# SOC_COMPHY_USB.net
KiCad netlist of a schematic drawn in Altium Designer
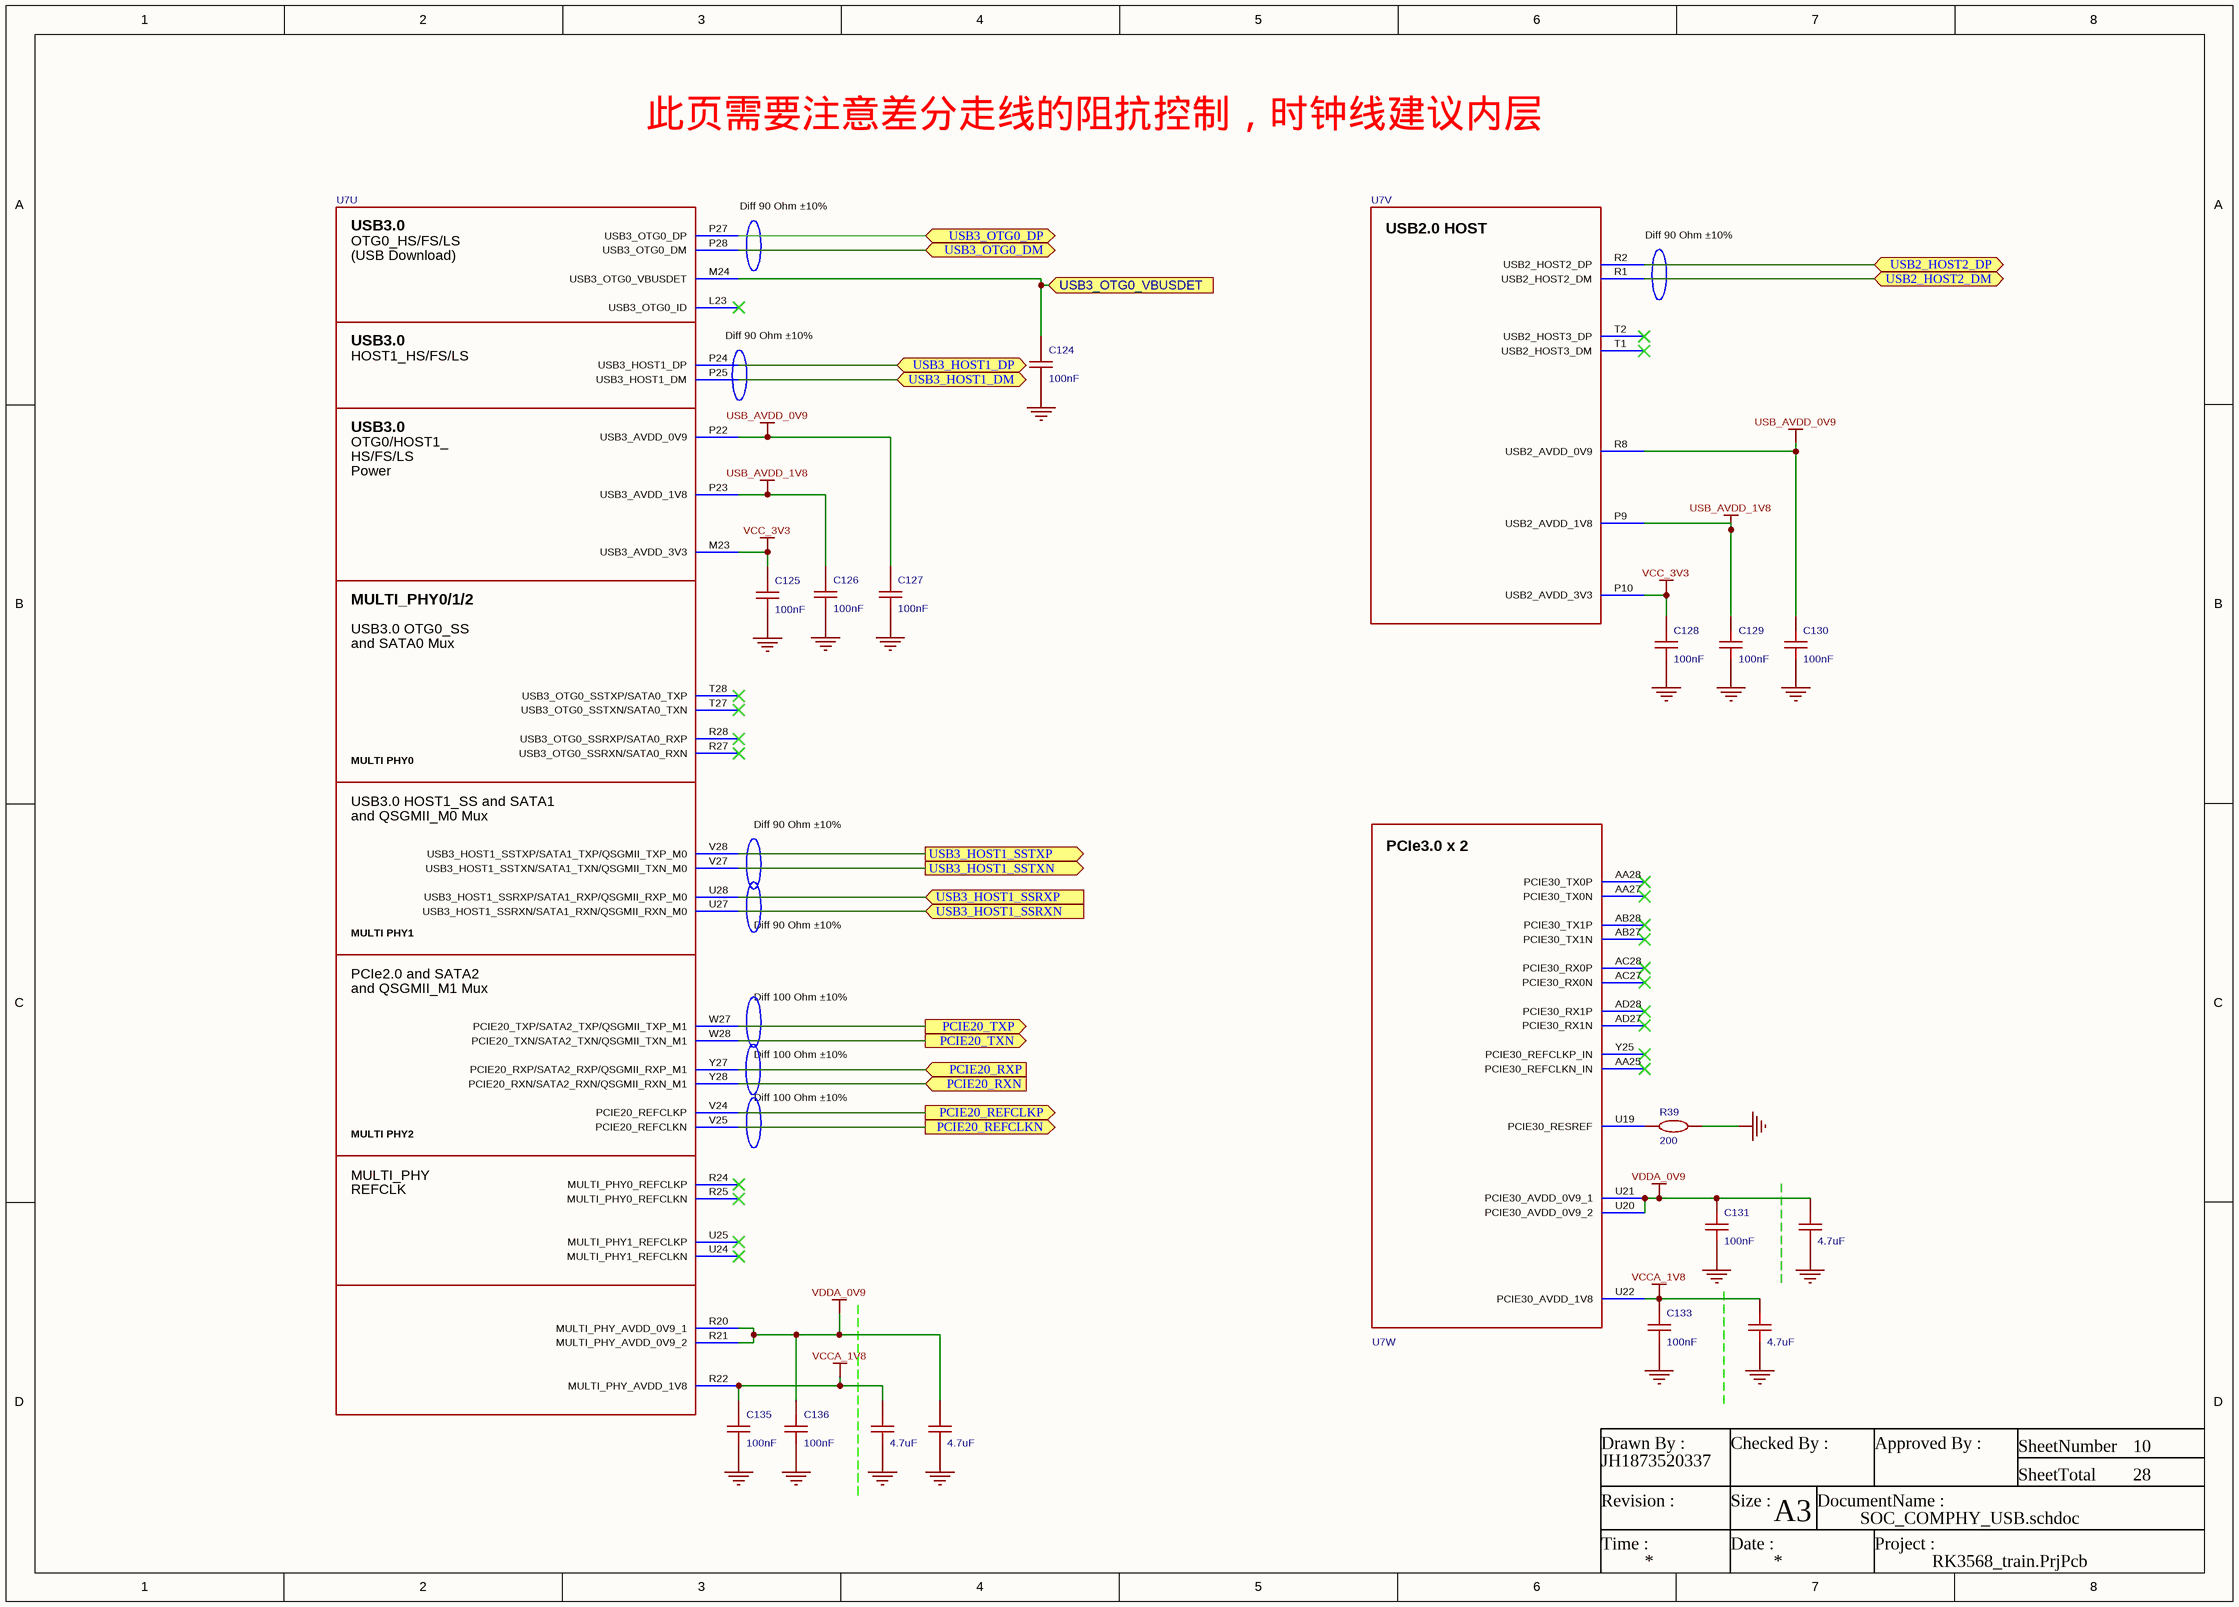
[diagram p0: SOC_COMPHY_USB.schdoc]

(export (version "E")
  (design (tool "Eeschema 10.0.6"))
  (components
    (comp (ref "C124")
      (value "100nF")
      (footprint "C0201")
      (description "容值:4.7uF;精度:±20%;额定电压:6.3V;温度系数:X5R;")
      (fields
        (field (name "MANUFACTURER") "muRata(村田)")
        (field (name "MANUFACTURERPART") "GRM035R60J475ME15D")
      )
      (libsource (lib "altium-import") (part "root_0_GRM035R60J475ME15D_"))
    )
    (comp (ref "C125")
      (value "100nF")
      (footprint "C0201")
      (description "容值:4.7uF;精度:±20%;额定电压:6.3V;温度系数:X5R;")
      (fields
        (field (name "MANUFACTURER") "muRata(村田)")
        (field (name "MANUFACTURERPART") "GRM035R60J475ME15D")
      )
      (libsource (lib "altium-import") (part "root_0_GRM035R60J475ME15D_"))
    )
    (comp (ref "C126")
      (value "100nF")
      (footprint "C0201")
      (description "容值:4.7uF;精度:±20%;额定电压:6.3V;温度系数:X5R;")
      (fields
        (field (name "MANUFACTURER") "muRata(村田)")
        (field (name "MANUFACTURERPART") "GRM035R60J475ME15D")
      )
      (libsource (lib "altium-import") (part "root_0_GRM035R60J475ME15D_"))
    )
    (comp (ref "C127")
      (value "100nF")
      (footprint "C0201")
      (description "容值:4.7uF;精度:±20%;额定电压:6.3V;温度系数:X5R;")
      (fields
        (field (name "MANUFACTURER") "muRata(村田)")
        (field (name "MANUFACTURERPART") "GRM035R60J475ME15D")
      )
      (libsource (lib "altium-import") (part "root_0_GRM035R60J475ME15D_"))
    )
    (comp (ref "C128")
      (value "100nF")
      (footprint "C0201")
      (description "容值:4.7uF;精度:±20%;额定电压:6.3V;温度系数:X5R;")
      (fields
        (field (name "MANUFACTURER") "muRata(村田)")
        (field (name "MANUFACTURERPART") "GRM035R60J475ME15D")
      )
      (libsource (lib "altium-import") (part "root_0_GRM035R60J475ME15D_"))
    )
    (comp (ref "C129")
      (value "100nF")
      (footprint "C0201")
      (description "容值:4.7uF;精度:±20%;额定电压:6.3V;温度系数:X5R;")
      (fields
        (field (name "MANUFACTURER") "muRata(村田)")
        (field (name "MANUFACTURERPART") "GRM035R60J475ME15D")
      )
      (libsource (lib "altium-import") (part "root_0_GRM035R60J475ME15D_"))
    )
    (comp (ref "C130")
      (value "100nF")
      (footprint "C0201")
      (description "容值:4.7uF;精度:±20%;额定电压:6.3V;温度系数:X5R;")
      (fields
        (field (name "MANUFACTURER") "muRata(村田)")
        (field (name "MANUFACTURERPART") "GRM035R60J475ME15D")
      )
      (libsource (lib "altium-import") (part "root_0_GRM035R60J475ME15D_"))
    )
    (comp (ref "C131")
      (value "100nF")
      (footprint "C0201")
      (description "容值:4.7uF;精度:±20%;额定电压:6.3V;温度系数:X5R;")
      (fields
        (field (name "MANUFACTURER") "muRata(村田)")
        (field (name "MANUFACTURERPART") "GRM035R60J475ME15D")
      )
      (libsource (lib "altium-import") (part "root_0_GRM035R60J475ME15D_"))
    )
    (comp (ref "C132")
      (value "4.7uF")
      (footprint "MYC0402")
      (description "容值:1uF;精度:±10%;额定电压:50V;材质(温度系数):X5R;")
      (fields (field (name "MANUFACTURER") "SAMSUNG(三星)") (field (name "MANUFACTURERPART") "CL10A105KB8NNNC"))
      (libsource (lib "altium-import") (part "root_1_CL10A105KB8NNNC_"))
    )
    (comp (ref "C133")
      (value "100nF")
      (footprint "C0201")
      (description "容值:4.7uF;精度:±20%;额定电压:6.3V;温度系数:X5R;")
      (fields
        (field (name "MANUFACTURER") "muRata(村田)")
        (field (name "MANUFACTURERPART") "GRM035R60J475ME15D")
      )
      (libsource (lib "altium-import") (part "root_0_GRM035R60J475ME15D_"))
    )
    (comp (ref "C134")
      (value "4.7uF")
      (footprint "MYC0402")
      (description "容值:1uF;精度:±10%;额定电压:50V;材质(温度系数):X5R;")
      (fields (field (name "MANUFACTURER") "SAMSUNG(三星)") (field (name "MANUFACTURERPART") "CL10A105KB8NNNC"))
      (libsource (lib "altium-import") (part "root_1_CL10A105KB8NNNC_"))
    )
    (comp (ref "C135")
      (value "100nF")
      (footprint "C0201")
      (description "容值:4.7uF;精度:±20%;额定电压:6.3V;温度系数:X5R;")
      (fields
        (field (name "MANUFACTURER") "muRata(村田)")
        (field (name "MANUFACTURERPART") "GRM035R60J475ME15D")
      )
      (libsource (lib "altium-import") (part "root_0_GRM035R60J475ME15D_"))
    )
    (comp (ref "C136")
      (value "100nF")
      (footprint "C0201")
      (description "容值:4.7uF;精度:±20%;额定电压:6.3V;温度系数:X5R;")
      (fields
        (field (name "MANUFACTURER") "muRata(村田)")
        (field (name "MANUFACTURERPART") "GRM035R60J475ME15D")
      )
      (libsource (lib "altium-import") (part "root_0_GRM035R60J475ME15D_"))
    )
    (comp (ref "C137")
      (value "4.7uF")
      (footprint "MYC0402")
      (description "容值:1uF;精度:±10%;额定电压:50V;材质(温度系数):X5R;")
      (fields (field (name "MANUFACTURER") "SAMSUNG(三星)") (field (name "MANUFACTURERPART") "CL10A105KB8NNNC"))
      (libsource (lib "altium-import") (part "root_1_CL10A105KB8NNNC_"))
    )
    (comp (ref "C138")
      (value "4.7uF")
      (footprint "MYC0402")
      (description "容值:1uF;精度:±10%;额定电压:50V;材质(温度系数):X5R;")
      (fields (field (name "MANUFACTURER") "SAMSUNG(三星)") (field (name "MANUFACTURERPART") "CL10A105KB8NNNC"))
      (libsource (lib "altium-import") (part "root_1_CL10A105KB8NNNC_"))
    )
    (comp (ref "R39")
      (value "200")
      (footprint "R0201")
      (libsource (lib "altium-import") (part "root_0_Res_0201_"))
    )
    (comp (ref "U7")
      (value "RK3568")
      (footprint "BGA-636_L19.0-W19.0-P0.65-BL")
      (libsource (lib "altium-import") (part "root_0_RK3568_"))
    )
  )
  (nets
    (net (code "1") (name "/PCIE20_REFCLKN") (class "Default")
      (node (ref "U7") (pin "V25") (pinfunction "PCIE20_REFCLKN_V25") (pintype "passive"))
    )
    (net (code "2") (name "/PCIE20_REFCLKP") (class "Default")
      (node (ref "U7") (pin "V24") (pinfunction "PCIE20_REFCLKP_V24") (pintype "passive"))
    )
    (net (code "3") (name "/PCIE20_RXN") (class "Default")
      (node (ref "U7") (pin "Y28") (pinfunction "PCIE20_RXN/SATA2_RXN/QSGMII_RXN_M1_Y28") (pintype "passive"))
    )
    (net (code "4") (name "/PCIE20_RXP") (class "Default")
      (node (ref "U7") (pin "Y27") (pinfunction "PCIE20_RXP/SATA2_RXP/QSGMII_RXP_M1_Y27") (pintype "passive"))
    )
    (net (code "5") (name "/PCIE20_TXN") (class "Default")
      (node (ref "U7") (pin "W28") (pinfunction "PCIE20_TXN/SATA2_TXN/QSGMII_TXN_M1_W28") (pintype "passive"))
    )
    (net (code "6") (name "/PCIE20_TXP") (class "Default")
      (node (ref "U7") (pin "W27") (pinfunction "PCIE20_TXP/SATA2_TXP/QSGMII_TXP_M1_W27") (pintype "passive"))
    )
    (net (code "7") (name "/USB2_HOST2_DM") (class "Default")
      (node (ref "U7") (pin "R1") (pinfunction "USB2_HOST2_DM_R1") (pintype "passive"))
    )
    (net (code "8") (name "/USB2_HOST2_DP") (class "Default")
      (node (ref "U7") (pin "R2") (pinfunction "USB2_HOST2_DP_R2") (pintype "passive"))
    )
    (net (code "9") (name "/USB3_HOST1_DM") (class "Default")
      (node (ref "U7") (pin "P25") (pinfunction "USB3_HOST1_DM_P25") (pintype "passive"))
    )
    (net (code "10") (name "/USB3_HOST1_DP") (class "Default")
      (node (ref "U7") (pin "P24") (pinfunction "USB3_HOST1_DP_P24") (pintype "passive"))
    )
    (net (code "11") (name "/USB3_HOST1_SSRXN") (class "Default")
      (node (ref "U7") (pin "U27") (pinfunction "USB3_HOST1_SSRXN/SATA1_RXN/QSGMII_RXN_M0_U27") (pintype "passive"))
    )
    (net (code "12") (name "/USB3_HOST1_SSRXP") (class "Default")
      (node (ref "U7") (pin "U28") (pinfunction "USB3_HOST1_SSRXP/SATA1_RXP/QSGMII_RXP_M0_U28") (pintype "passive"))
    )
    (net (code "13") (name "/USB3_HOST1_SSTXN") (class "Default")
      (node (ref "U7") (pin "V27") (pinfunction "USB3_HOST1_SSTXN/SATA1_TXN/QSGMII_TXN_M0_V27") (pintype "passive"))
    )
    (net (code "14") (name "/USB3_HOST1_SSTXP") (class "Default")
      (node (ref "U7") (pin "V28") (pinfunction "USB3_HOST1_SSTXP/SATA1_TXP/QSGMII_TXP_M0_V28") (pintype "passive"))
    )
    (net (code "15") (name "/USB3_OTG0_DM") (class "Default")
      (node (ref "U7") (pin "P28") (pinfunction "USB3_OTG0_DM_P28") (pintype "passive"))
    )
    (net (code "16") (name "/USB3_OTG0_DP") (class "Default")
      (node (ref "U7") (pin "P27") (pinfunction "USB3_OTG0_DP_P27") (pintype "passive"))
    )
    (net (code "17") (name "/USB3_OTG0_VBUSDET") (class "Default")
      (node (ref "C124") (pin "2") (pinfunction "2_2") (pintype "passive"))
      (node (ref "U7") (pin "M24") (pinfunction "USB3_OTG0_VBUSDET_M24") (pintype "passive"))
    )
    (net (code "18") (name "GND") (class "Default")
      (node (ref "C124") (pin "1") (pinfunction "1_1") (pintype "passive"))
      (node (ref "C125") (pin "1") (pinfunction "1_1") (pintype "passive"))
      (node (ref "C126") (pin "1") (pinfunction "1_1") (pintype "passive"))
      (node (ref "C127") (pin "1") (pinfunction "1_1") (pintype "passive"))
      (node (ref "C128") (pin "1") (pinfunction "1_1") (pintype "passive"))
      (node (ref "C129") (pin "1") (pinfunction "1_1") (pintype "passive"))
      (node (ref "C130") (pin "1") (pinfunction "1_1") (pintype "passive"))
      (node (ref "C131") (pin "1") (pinfunction "1_1") (pintype "passive"))
      (node (ref "C132") (pin "1") (pinfunction "1_1") (pintype "passive"))
      (node (ref "C133") (pin "1") (pinfunction "1_1") (pintype "passive"))
      (node (ref "C134") (pin "1") (pinfunction "1_1") (pintype "passive"))
      (node (ref "C135") (pin "1") (pinfunction "1_1") (pintype "passive"))
      (node (ref "C136") (pin "1") (pinfunction "1_1") (pintype "passive"))
      (node (ref "C137") (pin "1") (pinfunction "1_1") (pintype "passive"))
      (node (ref "C138") (pin "1") (pinfunction "1_1") (pintype "passive"))
      (node (ref "R39") (pin "2") (pinfunction "2_2") (pintype "passive"))
    )
    (net (code "19") (name "Net-(U7W-PCIE30_RESREF)") (class "Default")
      (node (ref "R39") (pin "1") (pinfunction "1_1") (pintype "passive"))
      (node (ref "U7") (pin "U19") (pinfunction "PCIE30_RESREF_U19") (pintype "passive"))
    )
    (net (code "20") (name "USB_AVDD_0V9") (class "Default")
      (node (ref "C127") (pin "2") (pinfunction "2_2") (pintype "passive"))
      (node (ref "C130") (pin "2") (pinfunction "2_2") (pintype "passive"))
      (node (ref "U7") (pin "P22") (pinfunction "USB3_AVDD_0V9_P22") (pintype "passive"))
      (node (ref "U7") (pin "R8") (pinfunction "USB2_AVDD_0V9_R8") (pintype "passive"))
    )
    (net (code "21") (name "USB_AVDD_1V8") (class "Default")
      (node (ref "C126") (pin "2") (pinfunction "2_2") (pintype "passive"))
      (node (ref "C129") (pin "2") (pinfunction "2_2") (pintype "passive"))
      (node (ref "U7") (pin "P23") (pinfunction "USB3_AVDD_1V8_P23") (pintype "passive"))
      (node (ref "U7") (pin "P9") (pinfunction "USB2_AVDD_1V8_P9") (pintype "passive"))
    )
    (net (code "22") (name "VCCA_1V8") (class "Default")
      (node (ref "C133") (pin "2") (pinfunction "2_2") (pintype "passive"))
      (node (ref "C134") (pin "2") (pinfunction "2_2") (pintype "passive"))
      (node (ref "C135") (pin "2") (pinfunction "2_2") (pintype "passive"))
      (node (ref "C137") (pin "2") (pinfunction "2_2") (pintype "passive"))
      (node (ref "U7") (pin "R22") (pinfunction "MULTI_PHY_AVDD_1V8_R22") (pintype "passive"))
      (node (ref "U7") (pin "U22") (pinfunction "PCIE30_AVDD_1V8_U22") (pintype "passive"))
    )
    (net (code "23") (name "VCC_3V3") (class "Default")
      (node (ref "C125") (pin "2") (pinfunction "2_2") (pintype "passive"))
      (node (ref "C128") (pin "2") (pinfunction "2_2") (pintype "passive"))
      (node (ref "U7") (pin "M23") (pinfunction "USB3_AVDD_3V3_M23") (pintype "passive"))
      (node (ref "U7") (pin "P10") (pinfunction "USB2_AVDD_3V3_P10") (pintype "passive"))
    )
    (net (code "24") (name "VDDA_0V9") (class "Default")
      (node (ref "C131") (pin "2") (pinfunction "2_2") (pintype "passive"))
      (node (ref "C132") (pin "2") (pinfunction "2_2") (pintype "passive"))
      (node (ref "C136") (pin "2") (pinfunction "2_2") (pintype "passive"))
      (node (ref "C138") (pin "2") (pinfunction "2_2") (pintype "passive"))
      (node (ref "U7") (pin "R20") (pinfunction "MULTI_PHY_AVDD_0V9_1_R20") (pintype "passive"))
      (node (ref "U7") (pin "R21") (pinfunction "MULTI_PHY_AVDD_0V9_2_R21") (pintype "passive"))
      (node (ref "U7") (pin "U20") (pinfunction "PCIE30_AVDD_0V9_2_U20") (pintype "passive"))
      (node (ref "U7") (pin "U21") (pinfunction "PCIE30_AVDD_0V9_1_U21") (pintype "passive"))
    )
    (net (code "25") (name "unconnected-(U7U-MULTI_PHY0_REFCLKN-PadR25)") (class "Default")
      (node (ref "U7") (pin "R25") (pinfunction "MULTI_PHY0_REFCLKN_R25") (pintype "passive+no_connect"))
    )
    (net (code "26") (name "unconnected-(U7U-MULTI_PHY0_REFCLKP-PadR24)") (class "Default")
      (node (ref "U7") (pin "R24") (pinfunction "MULTI_PHY0_REFCLKP_R24") (pintype "passive+no_connect"))
    )
    (net (code "27") (name "unconnected-(U7U-MULTI_PHY1_REFCLKN-PadU24)") (class "Default")
      (node (ref "U7") (pin "U24") (pinfunction "MULTI_PHY1_REFCLKN_U24") (pintype "passive+no_connect"))
    )
    (net (code "28") (name "unconnected-(U7U-MULTI_PHY1_REFCLKP-PadU25)") (class "Default")
      (node (ref "U7") (pin "U25") (pinfunction "MULTI_PHY1_REFCLKP_U25") (pintype "passive+no_connect"))
    )
    (net (code "29") (name "unconnected-(U7U-USB3_OTG0_ID-PadL23)") (class "Default")
      (node (ref "U7") (pin "L23") (pinfunction "USB3_OTG0_ID_L23") (pintype "passive+no_connect"))
    )
    (net (code "30") (name "unconnected-(U7U-USB3_OTG0_SSRXN{slash}SATA0_RXN-PadR27)") (class "Default")
      (node (ref "U7") (pin "R27") (pinfunction "USB3_OTG0_SSRXN/SATA0_RXN_R27") (pintype "passive+no_connect"))
    )
    (net (code "31") (name "unconnected-(U7U-USB3_OTG0_SSRXP{slash}SATA0_RXP-PadR28)") (class "Default")
      (node (ref "U7") (pin "R28") (pinfunction "USB3_OTG0_SSRXP/SATA0_RXP_R28") (pintype "passive+no_connect"))
    )
    (net (code "32") (name "unconnected-(U7U-USB3_OTG0_SSTXN{slash}SATA0_TXN-PadT27)") (class "Default")
      (node (ref "U7") (pin "T27") (pinfunction "USB3_OTG0_SSTXN/SATA0_TXN_T27") (pintype "passive+no_connect"))
    )
    (net (code "33") (name "unconnected-(U7U-USB3_OTG0_SSTXP{slash}SATA0_TXP-PadT28)") (class "Default")
      (node (ref "U7") (pin "T28") (pinfunction "USB3_OTG0_SSTXP/SATA0_TXP_T28") (pintype "passive+no_connect"))
    )
    (net (code "34") (name "unconnected-(U7V-USB2_HOST3_DM-PadT1)") (class "Default")
      (node (ref "U7") (pin "T1") (pinfunction "USB2_HOST3_DM_T1") (pintype "passive+no_connect"))
    )
    (net (code "35") (name "unconnected-(U7V-USB2_HOST3_DP-PadT2)") (class "Default")
      (node (ref "U7") (pin "T2") (pinfunction "USB2_HOST3_DP_T2") (pintype "passive+no_connect"))
    )
    (net (code "36") (name "unconnected-(U7W-PCIE30_REFCLKN_IN-PadAA25)") (class "Default")
      (node (ref "U7") (pin "AA25") (pinfunction "PCIE30_REFCLKN_IN_AA25") (pintype "passive+no_connect"))
    )
    (net (code "37") (name "unconnected-(U7W-PCIE30_REFCLKP_IN-PadY25)") (class "Default")
      (node (ref "U7") (pin "Y25") (pinfunction "PCIE30_REFCLKP_IN_Y25") (pintype "passive+no_connect"))
    )
    (net (code "38") (name "unconnected-(U7W-PCIE30_RX0N-PadAC27)") (class "Default")
      (node (ref "U7") (pin "AC27") (pinfunction "PCIE30_RX0N_AC27") (pintype "passive+no_connect"))
    )
    (net (code "39") (name "unconnected-(U7W-PCIE30_RX0P-PadAC28)") (class "Default")
      (node (ref "U7") (pin "AC28") (pinfunction "PCIE30_RX0P_AC28") (pintype "passive+no_connect"))
    )
    (net (code "40") (name "unconnected-(U7W-PCIE30_RX1N-PadAD27)") (class "Default")
      (node (ref "U7") (pin "AD27") (pinfunction "PCIE30_RX1N_AD27") (pintype "passive+no_connect"))
    )
    (net (code "41") (name "unconnected-(U7W-PCIE30_RX1P-PadAD28)") (class "Default")
      (node (ref "U7") (pin "AD28") (pinfunction "PCIE30_RX1P_AD28") (pintype "passive+no_connect"))
    )
    (net (code "42") (name "unconnected-(U7W-PCIE30_TX0N-PadAA27)") (class "Default")
      (node (ref "U7") (pin "AA27") (pinfunction "PCIE30_TX0N_AA27") (pintype "passive+no_connect"))
    )
    (net (code "43") (name "unconnected-(U7W-PCIE30_TX0P-PadAA28)") (class "Default")
      (node (ref "U7") (pin "AA28") (pinfunction "PCIE30_TX0P_AA28") (pintype "passive+no_connect"))
    )
    (net (code "44") (name "unconnected-(U7W-PCIE30_TX1N-PadAB27)") (class "Default")
      (node (ref "U7") (pin "AB27") (pinfunction "PCIE30_TX1N_AB27") (pintype "passive+no_connect"))
    )
    (net (code "45") (name "unconnected-(U7W-PCIE30_TX1P-PadAB28)") (class "Default")
      (node (ref "U7") (pin "AB28") (pinfunction "PCIE30_TX1P_AB28") (pintype "passive+no_connect"))
    )
  )
)
